# AIRZAI_LED_SENSE_FLEX_REVB.net
KiCad netlist of a schematic drawn in Altium Designer
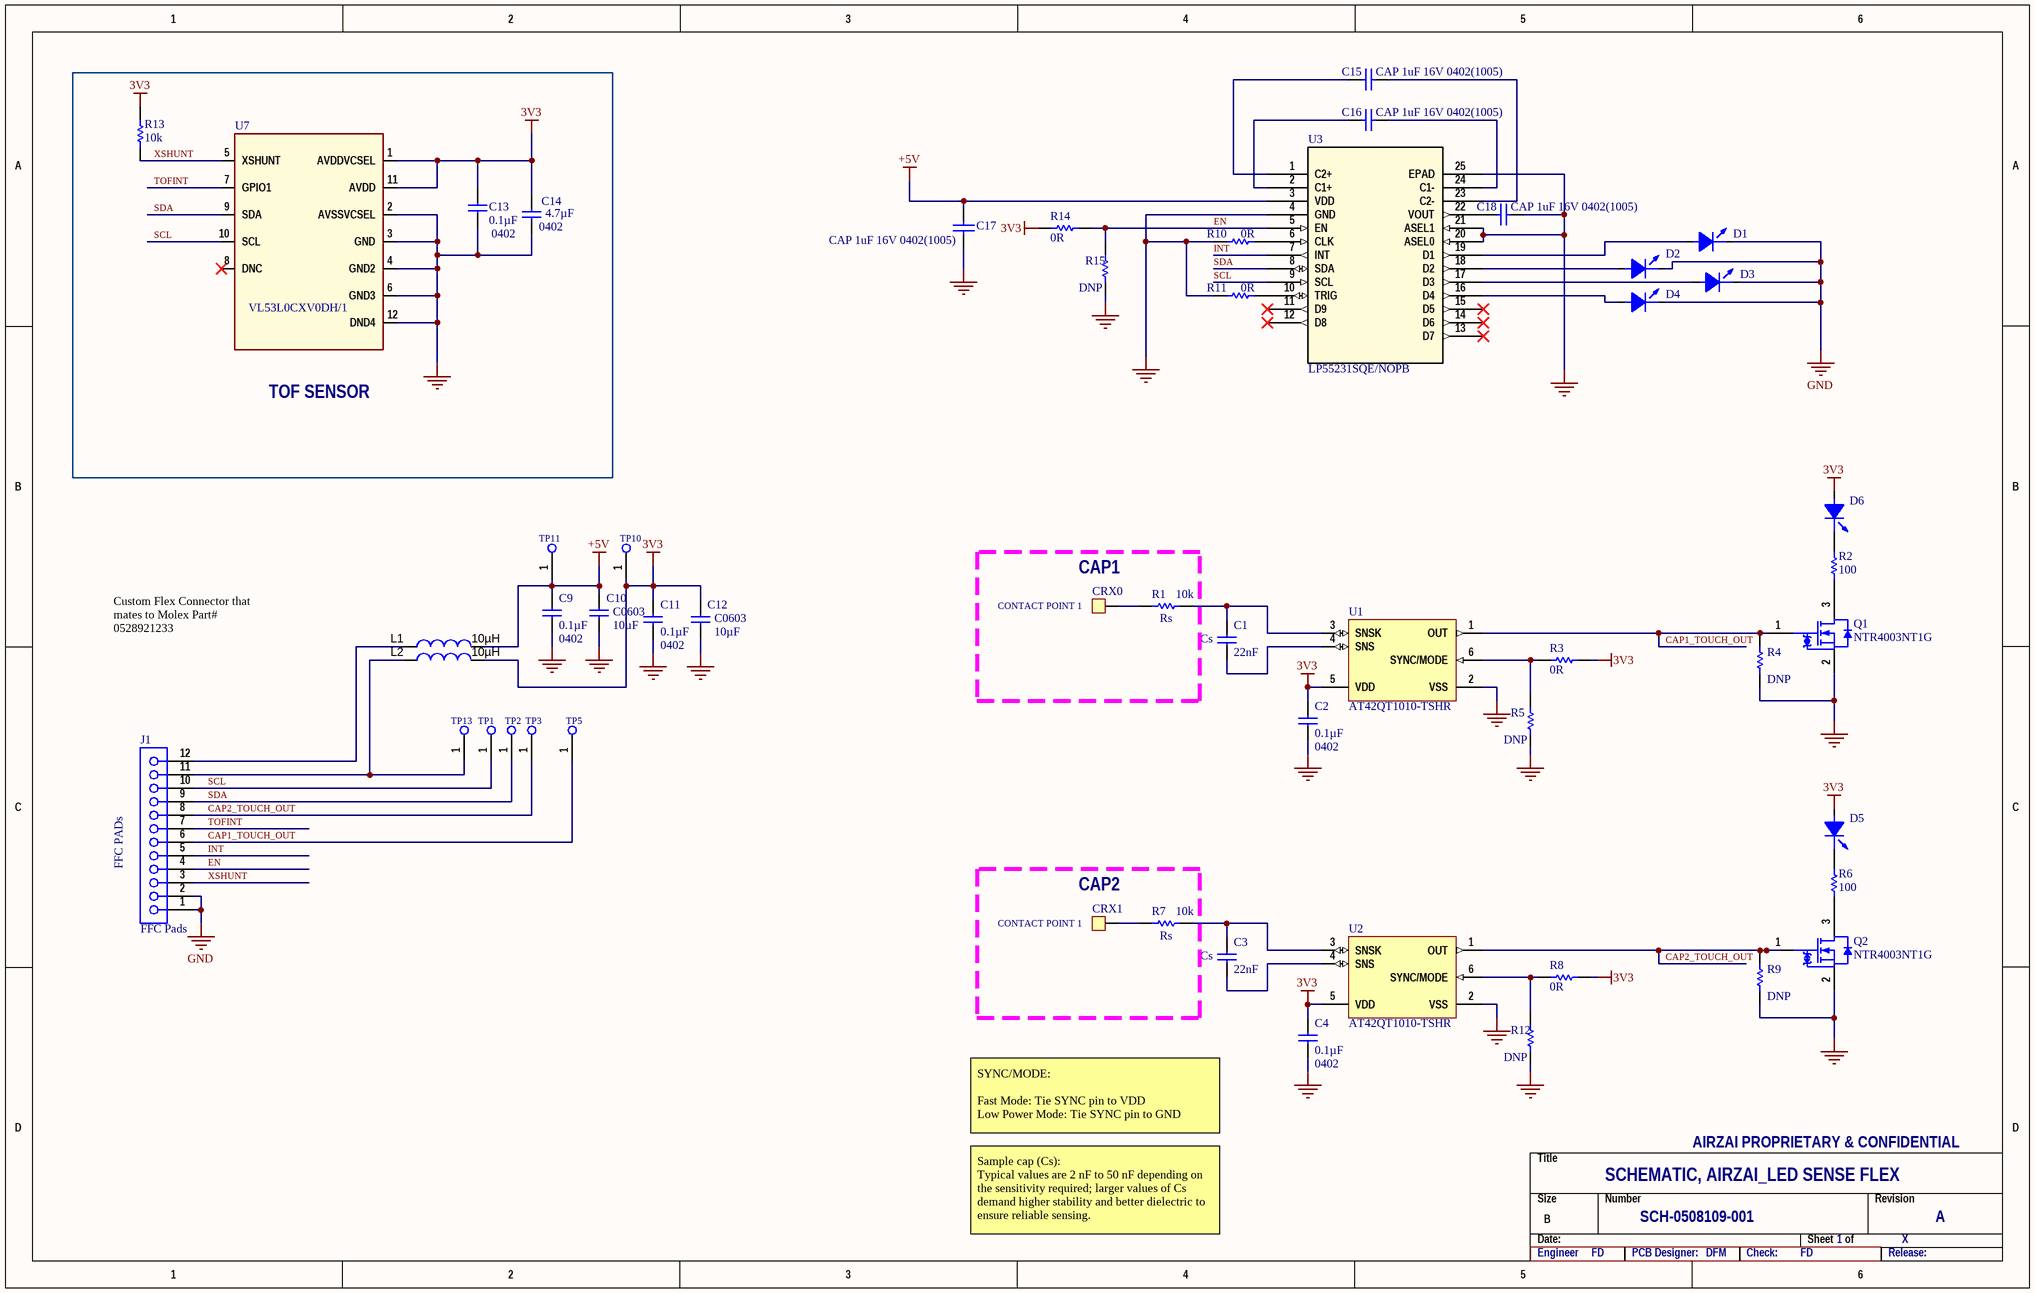
[diagram p0: AIRZAI_LED_SENSE_FLEX_REVB.SchDoc]

(export (version "E")
  (design (tool "Eeschema 10.0.6"))
  (components
    (comp (ref "C1")
      (value "22nF")
      (footprint "0402CAP")
      (description "Capacitor, X7R, ±10%")
      (fields
        (field (name "MANUFACTURER") "TDK")
        (field (name "MANUFACTURER PART NUMBER") "CGA2B2X7R1E223K050BA")
      )
      (libsource (lib "Nordic Passive DB") (part "CAP"))
    )
    (comp (ref "C2")
      (value "0.1µF")
      (footprint "0402")
      (description "Capacitor, X7R, ±10%")
      (fields (field (name "MANUFACTURER") "TDK") (field (name "MANUFACTURER PART NUMBER") "C1005X7R1C104K"))
      (libsource (lib "Nordic Passive DB") (part "CAP"))
    )
    (comp (ref "C3")
      (value "22nF")
      (footprint "0402CAP")
      (description "Capacitor, X7R, ±10%")
      (fields
        (field (name "MANUFACTURER") "TDK")
        (field (name "MANUFACTURER PART NUMBER") "CGA2B2X7R1E223K050BA")
      )
      (libsource (lib "Nordic Passive DB") (part "CAP"))
    )
    (comp (ref "C4")
      (value "0.1µF")
      (footprint "0402")
      (description "Capacitor, X7R, ±10%")
      (fields (field (name "MANUFACTURER") "TDK") (field (name "MANUFACTURER PART NUMBER") "C1005X7R1C104K"))
      (libsource (lib "Nordic Passive DB") (part "CAP"))
    )
    (comp (ref "C9")
      (value "0.1µF")
      (footprint "0402")
      (description "Capacitor, X7R, ±10%")
      (fields (field (name "MANUFACTURER") "TDK") (field (name "MANUFACTURER PART NUMBER") "C1005X7R1C104K"))
      (libsource (lib "Nordic Passive DB") (part "CAP"))
    )
    (comp (ref "C10")
      (value "10µF")
      (footprint "C0603")
      (description "Capacitor, X7R, ±10%")
      (fields
        (field (name "MANUFACTURER") "MURATA")
        (field (name "MANUFACTURER PART NUMBER") "GRM188R60J106ME47D")
      )
      (libsource (lib "Nordic Passive DB") (part "CAP"))
    )
    (comp (ref "C11")
      (value "0.1µF")
      (footprint "0402")
      (description "Capacitor, X7R, ±10%")
      (fields (field (name "MANUFACTURER") "TDK") (field (name "MANUFACTURER PART NUMBER") "C1005X7R1C104K"))
      (libsource (lib "Nordic Passive DB") (part "CAP"))
    )
    (comp (ref "C12")
      (value "10µF")
      (footprint "C0603")
      (description "Capacitor, X7R, ±10%")
      (fields
        (field (name "MANUFACTURER") "MURATA")
        (field (name "MANUFACTURER PART NUMBER") "GRM188R60J106ME47D")
      )
      (libsource (lib "Nordic Passive DB") (part "CAP"))
    )
    (comp (ref "C13")
      (value "0.1µF")
      (footprint "0402")
      (description "Capacitor, X7R, ±10%")
      (fields (field (name "MANUFACTURER") "TDK") (field (name "MANUFACTURER PART NUMBER") "C1005X7R1C104K"))
      (libsource (lib "Nordic Passive DB") (part "CAP"))
    )
    (comp (ref "C14")
      (value "4.7µF")
      (footprint "0402")
      (description "Capacitor, X7R, ±10%")
      (fields (field (name "MANUFACTURER") "TDK") (field (name "MANUFACTURER PART NUMBER") "C1005X5R0J475M"))
      (libsource (lib "Nordic Passive DB") (part "CAP"))
    )
    (comp (ref "C15")
      (value "CAP 1uF 16V 0402(1005)")
      (footprint "CAPC0402(1005)60_M")
      (description "CAP 1uF 16V ±10% 0402 (1005 Metric) Thickness 0.6mm SMD")
      (fields (field (name "TOLERANCE") "Â±10%") (field (name "MANUFACTURER") "Taiyo Yuden"))
      (libsource (lib "AIRZAI_LED_SENSE_FLEX_REVA") (part "CAP"))
    )
    (comp (ref "C16")
      (value "CAP 1uF 16V 0402(1005)")
      (footprint "CAPC0402(1005)60_M")
      (description "CAP 1uF 16V ±10% 0402 (1005 Metric) Thickness 0.6mm SMD")
      (fields (field (name "TOLERANCE") "Â±10%") (field (name "MANUFACTURER") "Taiyo Yuden"))
      (libsource (lib "AIRZAI_LED_SENSE_FLEX_REVA") (part "CAP"))
    )
    (comp (ref "C17")
      (value "CAP 1uF 16V 0402(1005)")
      (footprint "CAPC0402(1005)60_M")
      (description "CAP 1uF 16V ±10% 0402 (1005 Metric) Thickness 0.6mm SMD")
      (fields (field (name "TOLERANCE") "Â±10%") (field (name "MANUFACTURER") "Taiyo Yuden"))
      (libsource (lib "AIRZAI_LED_SENSE_FLEX_REVA") (part "CAP"))
    )
    (comp (ref "C18")
      (value "CAP 1uF 16V 0402(1005)")
      (footprint "CAPC0402(1005)60_M")
      (description "CAP 1uF 16V ±10% 0402 (1005 Metric) Thickness 0.6mm SMD")
      (fields (field (name "TOLERANCE") "Â±10%") (field (name "MANUFACTURER") "Taiyo Yuden"))
      (libsource (lib "AIRZAI_LED_SENSE_FLEX_REVA") (part "CAP"))
    )
    (comp (ref "CRX0")
      (value "CONTACT POINT 1")
      (footprint "CONTACT_POINT_1CM _SQ - duplicate")
      (libsource (lib "AIRZAI_LED_SENSE_FLEX_REVA") (part "WIRE_POINT"))
    )
    (comp (ref "CRX1")
      (value "CONTACT POINT 1")
      (footprint "CONTACT_POINT_1CM _SQ")
      (libsource (lib "AIRZAI_LED_SENSE_FLEX_REVA") (part "WIRE_POINT"))
    )
    (comp (ref "D1")
      (value "WHITE")
      (footprint "LED1206_LTW-C230DS")
      (fields (field (name "MANUFACTURER PART NUMBER") "LTW-C230DS") (field (name "MANUFACTURER") "LITEON"))
      (libsource (lib "AIRZAI_LED_SENSE_FLEX_REVA") (part "LED_LTW-C230DS"))
    )
    (comp (ref "D2")
      (value "WHITE")
      (footprint "LED1206_LTW-C230DS")
      (fields (field (name "MANUFACTURER PART NUMBER") "LTW-C230DS") (field (name "MANUFACTURER") "LITEON"))
      (libsource (lib "AIRZAI_LED_SENSE_FLEX_REVA") (part "LED_LTW-C230DS"))
    )
    (comp (ref "D3")
      (value "WHITE")
      (footprint "LED1206_LTW-C230DS")
      (fields (field (name "MANUFACTURER PART NUMBER") "LTW-C230DS") (field (name "MANUFACTURER") "LITEON"))
      (libsource (lib "AIRZAI_LED_SENSE_FLEX_REVA") (part "LED_LTW-C230DS"))
    )
    (comp (ref "D4")
      (value "WHITE")
      (footprint "LED1206_LTW-C230DS")
      (fields (field (name "MANUFACTURER PART NUMBER") "LTW-C230DS") (field (name "MANUFACTURER") "LITEON"))
      (libsource (lib "AIRZAI_LED_SENSE_FLEX_REVA") (part "LED_LTW-C230DS"))
    )
    (comp (ref "D5")
      (value "WHITE")
      (footprint "LED1206_LTW-C230DS")
      (fields (field (name "MANUFACTURER PART NUMBER") "LTW-C230DS") (field (name "MANUFACTURER") "LITEON"))
      (libsource (lib "AIRZAI_LED_SENSE_FLEX_REVA") (part "LED_LTW-C230DS"))
    )
    (comp (ref "D6")
      (value "WHITE")
      (footprint "LED1206_LTW-C230DS")
      (fields (field (name "MANUFACTURER PART NUMBER") "LTW-C230DS") (field (name "MANUFACTURER") "LITEON"))
      (libsource (lib "AIRZAI_LED_SENSE_FLEX_REVA") (part "LED_LTW-C230DS"))
    )
    (comp (ref "J1")
      (value "FFC Pads")
      (footprint "FFC_Pads")
      (description "0.5 mm Pitch FFC Pads")
      (libsource (lib "AIRZAI_LED_SENSE_FLEX_REVA") (part "FFC_PADS"))
    )
    (comp (ref "L1")
      (value "CB2012T100KR")
      (footprint "0805")
      (description "Inductor, 10 µH, 0.5A, 0.65 ohm, SMD")
      (fields
        (field (name "MANUFACTURER") "Taiyo Yuden")
        (field (name "TOLERANCE") "10%")
        (field (name "VALUEDISPLAYED") "10µH")
      )
      (libsource (lib "AIRZAI_LED_SENSE_FLEX_REVA") (part "CB2012T100KR"))
    )
    (comp (ref "L2")
      (value "CB2012T100KR")
      (footprint "0805")
      (description "Inductor, 10 µH, 0.5A, 0.65 ohm, SMD")
      (fields
        (field (name "MANUFACTURER") "Taiyo Yuden")
        (field (name "TOLERANCE") "10%")
        (field (name "VALUEDISPLAYED") "10µH")
      )
      (libsource (lib "AIRZAI_LED_SENSE_FLEX_REVA") (part "CB2012T100KR"))
    )
    (comp (ref "Q1")
      (value "NTR4003NT1G")
      (footprint "SOT-23-3-NTR4003NT1G")
      (description "N-Channel 30V 500mA (Ta) 690mW (Ta) Surface Mount SOT-23-3 (TO-236)")
      (fields (field (name "MANUFACTURER") "ON Semiconductor"))
      (libsource (lib "AIRZAI_LED_SENSE_FLEX_REVA") (part "NTR4003NT1G"))
    )
    (comp (ref "Q2")
      (value "NTR4003NT1G")
      (footprint "SOT-23-3-NTR4003NT1G")
      (description "N-Channel 30V 500mA (Ta) 690mW (Ta) Surface Mount SOT-23-3 (TO-236)")
      (fields (field (name "MANUFACTURER") "ON Semiconductor"))
      (libsource (lib "AIRZAI_LED_SENSE_FLEX_REVA") (part "NTR4003NT1G"))
    )
    (comp (ref "R1")
      (value "10k")
      (footprint "0402")
      (description "10k 0.063W 1% 0402 (1005 Metric)  SMD")
      (fields (field (name "TOLERANCE") "None") (field (name "POWER") "0.063W"))
      (libsource (lib "AIRZAI_LED_SENSE_FLEX_REVA") (part "RES"))
    )
    (comp (ref "R2")
      (value "100")
      (footprint "0402")
      (description "100 0.063W 1% 0402 (1005 Metric)  SMD")
      (fields (field (name "TOLERANCE") "None") (field (name "MANUFACTURER") "Yageo"))
      (libsource (lib "AIRZAI_LED_SENSE_FLEX_REVA") (part "RES"))
    )
    (comp (ref "R3")
      (value "0R")
      (footprint "0402")
      (description "Jumper 0402 (1005 Metric)")
      (fields (field (name "TOLERANCE") "None") (field (name "MANUFACTURER") "Panasonic"))
      (libsource (lib "AIRZAI_LED_SENSE_FLEX_REVA") (part "RES"))
    )
    (comp (ref "R4")
      (value "DNP")
      (footprint "0402")
      (fields
        (field (name "TOLERANCE") "None")
        (field (name "POWER") "0.0625 W")
        (field (name "Comment") "DNP 0402(1005)")
      )
      (libsource (lib "AIRZAI_LED_SENSE_FLEX_REVA") (part "RES"))
    )
    (comp (ref "R5")
      (value "DNP")
      (footprint "0402")
      (fields
        (field (name "TOLERANCE") "None")
        (field (name "POWER") "0.0625 W")
        (field (name "Comment") "DNP 0402(1005)")
      )
      (libsource (lib "AIRZAI_LED_SENSE_FLEX_REVA") (part "RES"))
    )
    (comp (ref "R6")
      (value "100")
      (footprint "0402")
      (description "100 0.063W 1% 0402 (1005 Metric)  SMD")
      (fields (field (name "TOLERANCE") "None") (field (name "MANUFACTURER") "Yageo"))
      (libsource (lib "AIRZAI_LED_SENSE_FLEX_REVA") (part "RES"))
    )
    (comp (ref "R7")
      (value "10k")
      (footprint "0402")
      (description "10k 0.063W 1% 0402 (1005 Metric)  SMD")
      (fields (field (name "TOLERANCE") "None") (field (name "POWER") "0.063W"))
      (libsource (lib "AIRZAI_LED_SENSE_FLEX_REVA") (part "RES"))
    )
    (comp (ref "R8")
      (value "0R")
      (footprint "0402")
      (description "Jumper 0402 (1005 Metric)")
      (fields (field (name "TOLERANCE") "None") (field (name "MANUFACTURER") "Panasonic"))
      (libsource (lib "AIRZAI_LED_SENSE_FLEX_REVA") (part "RES"))
    )
    (comp (ref "R9")
      (value "DNP")
      (footprint "0402")
      (fields
        (field (name "TOLERANCE") "None")
        (field (name "POWER") "0.0625 W")
        (field (name "Comment") "DNP 0402(1005)")
      )
      (libsource (lib "AIRZAI_LED_SENSE_FLEX_REVA") (part "RES"))
    )
    (comp (ref "R10")
      (value "0R")
      (footprint "0402")
      (description "Jumper 0402 (1005 Metric)")
      (fields (field (name "TOLERANCE") "None") (field (name "MANUFACTURER") "Panasonic"))
      (libsource (lib "AIRZAI_LED_SENSE_FLEX_REVA") (part "RES"))
    )
    (comp (ref "R11")
      (value "0R")
      (footprint "0402")
      (description "Jumper 0402 (1005 Metric)")
      (fields (field (name "TOLERANCE") "None") (field (name "MANUFACTURER") "Panasonic"))
      (libsource (lib "AIRZAI_LED_SENSE_FLEX_REVA") (part "RES"))
    )
    (comp (ref "R12")
      (value "DNP")
      (footprint "0402")
      (fields
        (field (name "TOLERANCE") "None")
        (field (name "POWER") "0.0625 W")
        (field (name "Comment") "DNP 0402(1005)")
      )
      (libsource (lib "AIRZAI_LED_SENSE_FLEX_REVA") (part "RES"))
    )
    (comp (ref "R13")
      (value "10k")
      (footprint "0402")
      (description "10k 0.063W 1% 0402 (1005 Metric)  SMD")
      (fields (field (name "TOLERANCE") "None") (field (name "POWER") "0.063W"))
      (libsource (lib "AIRZAI_LED_SENSE_FLEX_REVA") (part "RES"))
    )
    (comp (ref "R14")
      (value "0R")
      (footprint "0402")
      (description "Jumper 0402 (1005 Metric)")
      (fields (field (name "TOLERANCE") "None") (field (name "MANUFACTURER") "Panasonic"))
      (libsource (lib "AIRZAI_LED_SENSE_FLEX_REVA") (part "RES"))
    )
    (comp (ref "R15")
      (value "DNP")
      (footprint "0402")
      (fields
        (field (name "TOLERANCE") "None")
        (field (name "POWER") "0.0625 W")
        (field (name "Comment") "DNP 0402(1005)")
      )
      (libsource (lib "AIRZAI_LED_SENSE_FLEX_REVA") (part "RES"))
    )
    (comp (ref "TP1")
      (value "Test Point")
      (footprint "TP_0.9MM")
      (libsource (lib "AIRZAI_LED_SENSE_FLEX_REVA") (part "Test Point"))
    )
    (comp (ref "TP2")
      (value "Test Point")
      (footprint "TP_0.9MM")
      (libsource (lib "AIRZAI_LED_SENSE_FLEX_REVA") (part "Test Point"))
    )
    (comp (ref "TP3")
      (value "Test Point")
      (footprint "TP_0.9MM")
      (libsource (lib "AIRZAI_LED_SENSE_FLEX_REVA") (part "Test Point"))
    )
    (comp (ref "TP5")
      (value "Test Point")
      (footprint "TP_0.9MM")
      (libsource (lib "AIRZAI_LED_SENSE_FLEX_REVA") (part "Test Point"))
    )
    (comp (ref "TP10")
      (value "Test Point")
      (footprint "TP_0.9MM")
      (libsource (lib "AIRZAI_LED_SENSE_FLEX_REVA") (part "Test Point"))
    )
    (comp (ref "TP11")
      (value "Test Point")
      (footprint "TP_0.9MM")
      (libsource (lib "AIRZAI_LED_SENSE_FLEX_REVA") (part "Test Point"))
    )
    (comp (ref "TP13")
      (value "Test Point")
      (footprint "TP_0.9MM")
      (libsource (lib "AIRZAI_LED_SENSE_FLEX_REVA") (part "Test Point"))
    )
    (comp (ref "U1")
      (value "AT42QT1010-TSHR")
      (footprint "SOT-23-6-AT42QT1010-TSHR")
      (description "One-channel Touch Sensor IC with Reset Timer, -40° to +85° C, 6-pin SOT23")
      (libsource (lib "AIRZAI_LED_SENSE_FLEX_REVA") (part "AT42QT1010-TSHR"))
    )
    (comp (ref "U2")
      (value "AT42QT1010-TSHR")
      (footprint "SOT-23-6-AT42QT1010-TSHR")
      (description "One-channel Touch Sensor IC with Reset Timer, -40° to +85° C, 6-pin SOT23")
      (libsource (lib "AIRZAI_LED_SENSE_FLEX_REVA") (part "AT42QT1010-TSHR"))
    )
    (comp (ref "U3")
      (value "LP55231SQE/NOPB")
      (footprint "WQFN-24-LP55231SQE/NOPB")
      (description "Imported")
      (fields (field (name "MANUFACTURER") "TI") (field (name "TOLERANCE") "None"))
      (libsource (lib "AltiumDesigner") (part "LP55231SQE/NOPB"))
    )
    (comp (ref "U7")
      (value "VL53L0CXV0DH/1")
      (footprint "VL53L0X")
      (fields (field (name "MANUFACTURER") "ST") (field (name "TOLERANCE") "None"))
      (libsource (lib "DFM_JBKEGSVS_Library") (part "VL53L0X"))
    )
  )
  (nets
    (net (code "1") (name "+5V") (class "Default")
      (node (ref "C10") (pin "1") (pinfunction "1_1") (pintype "passive"))
      (node (ref "C17") (pin "2") (pinfunction "2_2") (pintype "passive"))
      (node (ref "C9") (pin "1") (pinfunction "1_1") (pintype "passive"))
      (node (ref "L1") (pin "2") (pinfunction "2_2") (pintype "passive"))
      (node (ref "TP11") (pin "1") (pinfunction "1_1") (pintype "passive"))
      (node (ref "U3") (pin "3") (pinfunction "VDD_3") (pintype "power_in"))
    )
    (net (code "2") (name "/CAP1_TOUCH_OUT") (class "Default")
      (node (ref "J1") (pin "6") (pinfunction "6_6") (pintype "passive"))
      (node (ref "Q1") (pin "1") (pinfunction "G_1") (pintype "passive"))
      (node (ref "R4") (pin "1") (pinfunction "1_1") (pintype "passive"))
      (node (ref "TP5") (pin "1") (pinfunction "1_1") (pintype "passive"))
      (node (ref "U1") (pin "1") (pinfunction "OUT_1") (pintype "output"))
    )
    (net (code "3") (name "/CAP2_TOUCH_OUT") (class "Default")
      (node (ref "J1") (pin "8") (pinfunction "8_8") (pintype "passive"))
      (node (ref "Q2") (pin "1") (pinfunction "G_1") (pintype "passive"))
      (node (ref "R9") (pin "1") (pinfunction "1_1") (pintype "passive"))
      (node (ref "TP3") (pin "1") (pinfunction "1_1") (pintype "passive"))
      (node (ref "U2") (pin "1") (pinfunction "OUT_1") (pintype "output"))
    )
    (net (code "4") (name "/EN") (class "Default")
      (node (ref "J1") (pin "4") (pinfunction "4_4") (pintype "passive"))
      (node (ref "R14") (pin "2") (pinfunction "2_2") (pintype "passive"))
      (node (ref "R15") (pin "1") (pinfunction "1_1") (pintype "passive"))
      (node (ref "U3") (pin "5") (pinfunction "EN_5") (pintype "input"))
    )
    (net (code "5") (name "/INT") (class "Default")
      (node (ref "J1") (pin "5") (pinfunction "5_5") (pintype "passive"))
      (node (ref "U3") (pin "7") (pinfunction "INT_7") (pintype "output"))
    )
    (net (code "6") (name "/SCL") (class "Default")
      (node (ref "J1") (pin "10") (pinfunction "10_10") (pintype "passive"))
      (node (ref "TP1") (pin "1") (pinfunction "1_1") (pintype "passive"))
      (node (ref "U3") (pin "9") (pinfunction "SCL_9") (pintype "input"))
      (node (ref "U7") (pin "10") (pinfunction "SCL_10") (pintype "passive"))
    )
    (net (code "7") (name "/SDA") (class "Default")
      (node (ref "J1") (pin "9") (pinfunction "9_9") (pintype "passive"))
      (node (ref "TP2") (pin "1") (pinfunction "1_1") (pintype "passive"))
      (node (ref "U3") (pin "8") (pinfunction "SDA_8") (pintype "bidirectional"))
      (node (ref "U7") (pin "9") (pinfunction "SDA_9") (pintype "passive"))
    )
    (net (code "8") (name "/TOFINT") (class "Default")
      (node (ref "J1") (pin "7") (pinfunction "7_7") (pintype "passive"))
      (node (ref "U7") (pin "7") (pinfunction "GPIO1_7") (pintype "passive"))
    )
    (net (code "9") (name "/XSHUNT") (class "Default")
      (node (ref "J1") (pin "3") (pinfunction "3_3") (pintype "passive"))
      (node (ref "R13") (pin "2") (pinfunction "2_2") (pintype "passive"))
      (node (ref "U7") (pin "5") (pinfunction "XSHUNT_5") (pintype "passive"))
    )
    (net (code "10") (name "3V3") (class "Default")
      (node (ref "C11") (pin "1") (pinfunction "1_1") (pintype "passive"))
      (node (ref "C12") (pin "1") (pinfunction "1_1") (pintype "passive"))
      (node (ref "C13") (pin "1") (pinfunction "1_1") (pintype "passive"))
      (node (ref "C14") (pin "2") (pinfunction "2_2") (pintype "passive"))
      (node (ref "C2") (pin "1") (pinfunction "1_1") (pintype "passive"))
      (node (ref "C4") (pin "1") (pinfunction "1_1") (pintype "passive"))
      (node (ref "D5") (pin "2") (pinfunction "ANODE_2") (pintype "passive"))
      (node (ref "D6") (pin "2") (pinfunction "ANODE_2") (pintype "passive"))
      (node (ref "L2") (pin "2") (pinfunction "2_2") (pintype "passive"))
      (node (ref "R13") (pin "1") (pinfunction "1_1") (pintype "passive"))
      (node (ref "R14") (pin "1") (pinfunction "1_1") (pintype "passive"))
      (node (ref "R3") (pin "2") (pinfunction "2_2") (pintype "passive"))
      (node (ref "R8") (pin "2") (pinfunction "2_2") (pintype "passive"))
      (node (ref "TP10") (pin "1") (pinfunction "1_1") (pintype "passive"))
      (node (ref "U1") (pin "5") (pinfunction "VDD_5") (pintype "power_in"))
      (node (ref "U2") (pin "5") (pinfunction "VDD_5") (pintype "power_in"))
      (node (ref "U7") (pin "1") (pinfunction "AVDDVCSEL_1") (pintype "passive"))
      (node (ref "U7") (pin "11") (pinfunction "AVDD_11") (pintype "passive"))
    )
    (net (code "11") (name "GND") (class "Default")
      (node (ref "C10") (pin "2") (pinfunction "2_2") (pintype "passive"))
      (node (ref "C11") (pin "2") (pinfunction "2_2") (pintype "passive"))
      (node (ref "C12") (pin "2") (pinfunction "2_2") (pintype "passive"))
      (node (ref "C13") (pin "2") (pinfunction "2_2") (pintype "passive"))
      (node (ref "C14") (pin "1") (pinfunction "1_1") (pintype "passive"))
      (node (ref "C17") (pin "1") (pinfunction "1_1") (pintype "passive"))
      (node (ref "C18") (pin "2") (pinfunction "2_2") (pintype "passive"))
      (node (ref "C2") (pin "2") (pinfunction "2_2") (pintype "passive"))
      (node (ref "C4") (pin "2") (pinfunction "2_2") (pintype "passive"))
      (node (ref "C9") (pin "2") (pinfunction "2_2") (pintype "passive"))
      (node (ref "D1") (pin "1") (pinfunction "CATHODE_1") (pintype "passive"))
      (node (ref "D2") (pin "1") (pinfunction "CATHODE_1") (pintype "passive"))
      (node (ref "D3") (pin "1") (pinfunction "CATHODE_1") (pintype "passive"))
      (node (ref "D4") (pin "1") (pinfunction "CATHODE_1") (pintype "passive"))
      (node (ref "J1") (pin "1") (pinfunction "1_1") (pintype "passive"))
      (node (ref "J1") (pin "2") (pinfunction "2_2") (pintype "passive"))
      (node (ref "Q1") (pin "2") (pinfunction "S_2") (pintype "passive"))
      (node (ref "Q2") (pin "2") (pinfunction "S_2") (pintype "passive"))
      (node (ref "R10") (pin "1") (pinfunction "1_1") (pintype "passive"))
      (node (ref "R11") (pin "1") (pinfunction "1_1") (pintype "passive"))
      (node (ref "R12") (pin "2") (pinfunction "2_2") (pintype "passive"))
      (node (ref "R15") (pin "2") (pinfunction "2_2") (pintype "passive"))
      (node (ref "R4") (pin "2") (pinfunction "2_2") (pintype "passive"))
      (node (ref "R5") (pin "2") (pinfunction "2_2") (pintype "passive"))
      (node (ref "R9") (pin "2") (pinfunction "2_2") (pintype "passive"))
      (node (ref "U1") (pin "2") (pinfunction "VSS_2") (pintype "power_in"))
      (node (ref "U2") (pin "2") (pinfunction "VSS_2") (pintype "power_in"))
      (node (ref "U3") (pin "20") (pinfunction "ASEL0_20") (pintype "input"))
      (node (ref "U3") (pin "21") (pinfunction "ASEL1_21") (pintype "input"))
      (node (ref "U3") (pin "25") (pinfunction "EPAD_25") (pintype "passive"))
      (node (ref "U3") (pin "4") (pinfunction "GND_4") (pintype "power_in"))
      (node (ref "U7") (pin "12") (pinfunction "DND4_12") (pintype "passive"))
      (node (ref "U7") (pin "2") (pinfunction "AVSSVCSEL_2") (pintype "passive"))
      (node (ref "U7") (pin "3") (pinfunction "GND_3") (pintype "passive"))
      (node (ref "U7") (pin "4") (pinfunction "GND2_4") (pintype "passive"))
      (node (ref "U7") (pin "6") (pinfunction "GND3_6") (pintype "passive"))
    )
    (net (code "12") (name "Net-(CRX0-Pad1)") (class "Default")
      (node (ref "CRX0") (pin "1") (pinfunction "1_1") (pintype "passive"))
      (node (ref "R1") (pin "2") (pinfunction "2_2") (pintype "passive"))
    )
    (net (code "13") (name "Net-(CRX1-Pad1)") (class "Default")
      (node (ref "CRX1") (pin "1") (pinfunction "1_1") (pintype "passive"))
      (node (ref "R7") (pin "2") (pinfunction "2_2") (pintype "passive"))
    )
    (net (code "14") (name "Net-(D1-ANODE)") (class "Default")
      (node (ref "D1") (pin "2") (pinfunction "ANODE_2") (pintype "passive"))
      (node (ref "U3") (pin "19") (pinfunction "D1_19") (pintype "output"))
    )
    (net (code "15") (name "Net-(D2-ANODE)") (class "Default")
      (node (ref "D2") (pin "2") (pinfunction "ANODE_2") (pintype "passive"))
      (node (ref "U3") (pin "18") (pinfunction "D2_18") (pintype "output"))
    )
    (net (code "16") (name "Net-(D3-ANODE)") (class "Default")
      (node (ref "D3") (pin "2") (pinfunction "ANODE_2") (pintype "passive"))
      (node (ref "U3") (pin "17") (pinfunction "D3_17") (pintype "output"))
    )
    (net (code "17") (name "Net-(D4-ANODE)") (class "Default")
      (node (ref "D4") (pin "2") (pinfunction "ANODE_2") (pintype "passive"))
      (node (ref "U3") (pin "16") (pinfunction "D4_16") (pintype "output"))
    )
    (net (code "18") (name "Net-(D5-CATHODE)") (class "Default")
      (node (ref "D5") (pin "1") (pinfunction "CATHODE_1") (pintype "passive"))
      (node (ref "R6") (pin "2") (pinfunction "2_2") (pintype "passive"))
    )
    (net (code "19") (name "Net-(D6-CATHODE)") (class "Default")
      (node (ref "D6") (pin "1") (pinfunction "CATHODE_1") (pintype "passive"))
      (node (ref "R2") (pin "2") (pinfunction "2_2") (pintype "passive"))
    )
    (net (code "20") (name "Net-(J1-Pad11)") (class "Default")
      (node (ref "J1") (pin "11") (pinfunction "11_11") (pintype "passive"))
      (node (ref "L2") (pin "1") (pinfunction "1_1") (pintype "passive"))
      (node (ref "TP13") (pin "1") (pinfunction "1_1") (pintype "passive"))
    )
    (net (code "21") (name "Net-(J1-Pad12)") (class "Default")
      (node (ref "J1") (pin "12") (pinfunction "12_12") (pintype "passive"))
      (node (ref "L1") (pin "1") (pinfunction "1_1") (pintype "passive"))
    )
    (net (code "22") (name "Net-(Q1-D)") (class "Default")
      (node (ref "Q1") (pin "3") (pinfunction "D_3") (pintype "passive"))
      (node (ref "R2") (pin "1") (pinfunction "1_1") (pintype "passive"))
    )
    (net (code "23") (name "Net-(Q2-D)") (class "Default")
      (node (ref "Q2") (pin "3") (pinfunction "D_3") (pintype "passive"))
      (node (ref "R6") (pin "1") (pinfunction "1_1") (pintype "passive"))
    )
    (net (code "24") (name "Net-(U1-SNS)") (class "Default")
      (node (ref "C1") (pin "2") (pinfunction "2_2") (pintype "passive"))
      (node (ref "U1") (pin "4") (pinfunction "SNS_4") (pintype "bidirectional"))
    )
    (net (code "25") (name "Net-(U1-SNSK)") (class "Default")
      (node (ref "C1") (pin "1") (pinfunction "1_1") (pintype "passive"))
      (node (ref "R1") (pin "1") (pinfunction "1_1") (pintype "passive"))
      (node (ref "U1") (pin "3") (pinfunction "SNSK_3") (pintype "bidirectional"))
    )
    (net (code "26") (name "Net-(U1-SYNC{slash}MODE)") (class "Default")
      (node (ref "R3") (pin "1") (pinfunction "1_1") (pintype "passive"))
      (node (ref "R5") (pin "1") (pinfunction "1_1") (pintype "passive"))
      (node (ref "U1") (pin "6") (pinfunction "SYNC/MODE_6") (pintype "input"))
    )
    (net (code "27") (name "Net-(U2-SNS)") (class "Default")
      (node (ref "C3") (pin "2") (pinfunction "2_2") (pintype "passive"))
      (node (ref "U2") (pin "4") (pinfunction "SNS_4") (pintype "bidirectional"))
    )
    (net (code "28") (name "Net-(U2-SNSK)") (class "Default")
      (node (ref "C3") (pin "1") (pinfunction "1_1") (pintype "passive"))
      (node (ref "R7") (pin "1") (pinfunction "1_1") (pintype "passive"))
      (node (ref "U2") (pin "3") (pinfunction "SNSK_3") (pintype "bidirectional"))
    )
    (net (code "29") (name "Net-(U2-SYNC{slash}MODE)") (class "Default")
      (node (ref "R12") (pin "1") (pinfunction "1_1") (pintype "passive"))
      (node (ref "R8") (pin "1") (pinfunction "1_1") (pintype "passive"))
      (node (ref "U2") (pin "6") (pinfunction "SYNC/MODE_6") (pintype "input"))
    )
    (net (code "30") (name "Net-(U3-C1+)") (class "Default")
      (node (ref "C16") (pin "1") (pinfunction "1_1") (pintype "passive"))
      (node (ref "U3") (pin "2") (pinfunction "C1+_2") (pintype "passive"))
    )
    (net (code "31") (name "Net-(U3-C1-)") (class "Default")
      (node (ref "C16") (pin "2") (pinfunction "2_2") (pintype "passive"))
      (node (ref "U3") (pin "24") (pinfunction "C1-_24") (pintype "passive"))
    )
    (net (code "32") (name "Net-(U3-C2+)") (class "Default")
      (node (ref "C15") (pin "1") (pinfunction "1_1") (pintype "passive"))
      (node (ref "U3") (pin "1") (pinfunction "C2+_1") (pintype "passive"))
    )
    (net (code "33") (name "Net-(U3-C2-)") (class "Default")
      (node (ref "C15") (pin "2") (pinfunction "2_2") (pintype "passive"))
      (node (ref "U3") (pin "23") (pinfunction "C2-_23") (pintype "passive"))
    )
    (net (code "34") (name "Net-(U3-CLK)") (class "Default")
      (node (ref "R10") (pin "2") (pinfunction "2_2") (pintype "passive"))
      (node (ref "U3") (pin "6") (pinfunction "CLK_6") (pintype "input"))
    )
    (net (code "35") (name "Net-(U3-TRIG)") (class "Default")
      (node (ref "R11") (pin "2") (pinfunction "2_2") (pintype "passive"))
      (node (ref "U3") (pin "10") (pinfunction "TRIG_10") (pintype "bidirectional"))
    )
    (net (code "36") (name "Net-(U3-VOUT)") (class "Default")
      (node (ref "C18") (pin "1") (pinfunction "1_1") (pintype "passive"))
      (node (ref "U3") (pin "22") (pinfunction "VOUT_22") (pintype "output"))
    )
    (net (code "37") (name "unconnected-(U3-D5-Pad15)") (class "Default")
      (node (ref "U3") (pin "15") (pinfunction "D5_15") (pintype "output+no_connect"))
    )
    (net (code "38") (name "unconnected-(U3-D6-Pad14)") (class "Default")
      (node (ref "U3") (pin "14") (pinfunction "D6_14") (pintype "output+no_connect"))
    )
    (net (code "39") (name "unconnected-(U3-D7-Pad13)") (class "Default")
      (node (ref "U3") (pin "13") (pinfunction "D7_13") (pintype "output+no_connect"))
    )
    (net (code "40") (name "unconnected-(U3-D8-Pad12)") (class "Default")
      (node (ref "U3") (pin "12") (pinfunction "D8_12") (pintype "output+no_connect"))
    )
    (net (code "41") (name "unconnected-(U3-D9-Pad11)") (class "Default")
      (node (ref "U3") (pin "11") (pinfunction "D9_11") (pintype "output+no_connect"))
    )
    (net (code "42") (name "unconnected-(U7-DNC-Pad8)") (class "Default")
      (node (ref "U7") (pin "8") (pinfunction "DNC_8") (pintype "passive+no_connect"))
    )
  )
)
